# PWM.net
KiCad netlist of a schematic drawn in EAGLE
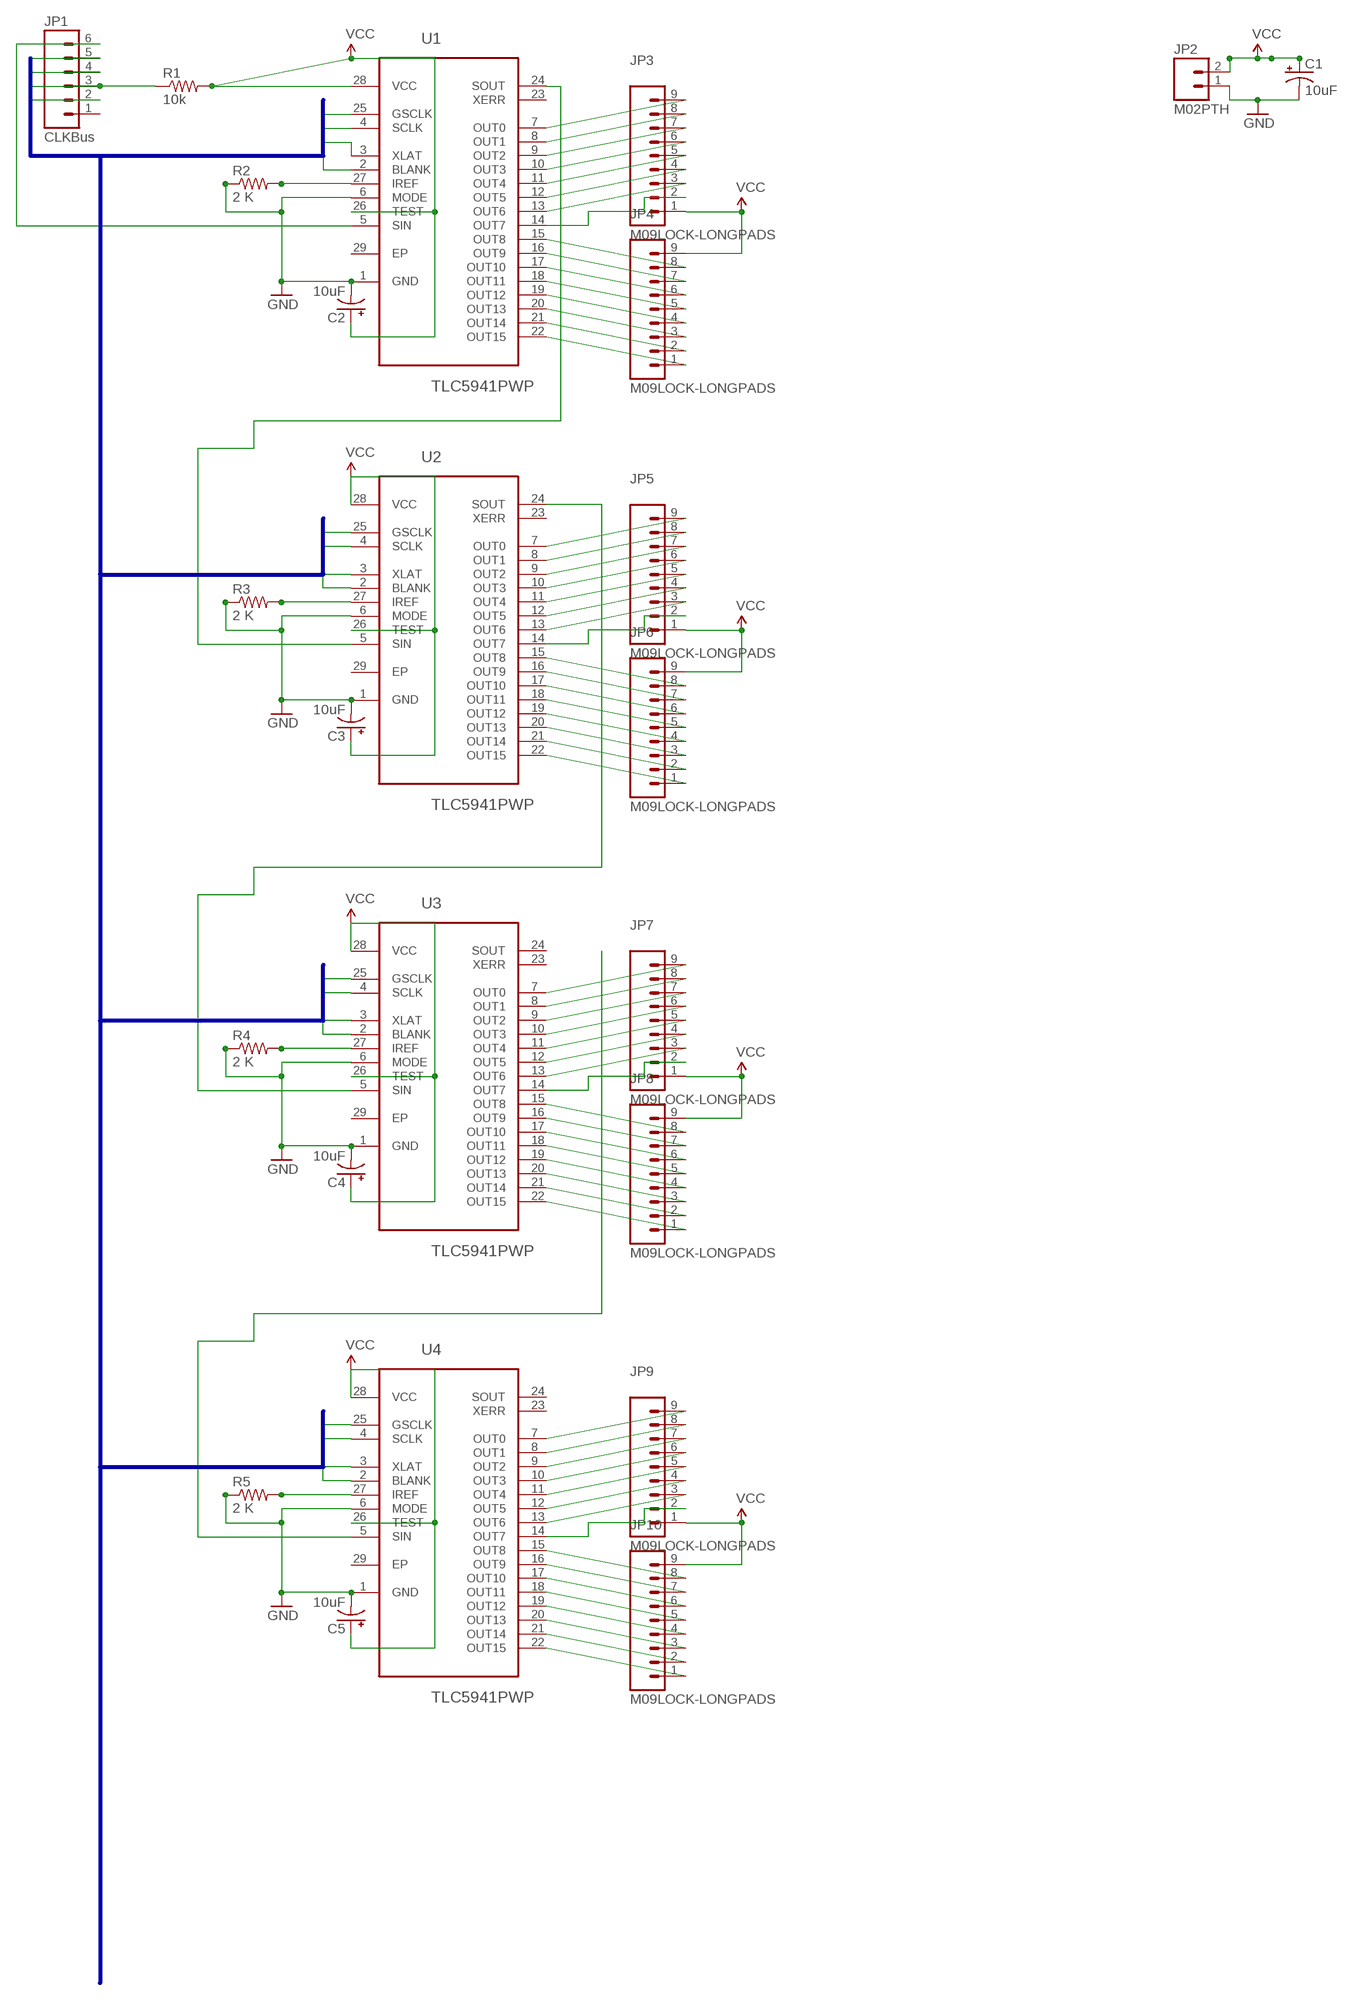
[diagram p0: schematic, sheet 1]

(export (version "E")
  (design (tool "Eeschema 10.0.6"))
  (components
    (comp (ref "C1")
      (value "10uF")
      (footprint "eagle-import:CPOL-RADIAL-10UF-25V")
      (libsource (lib "eagle-import") (part "CAP_POLPTH2"))
    )
    (comp (ref "C2")
      (value "10uF")
      (footprint "eagle-import:CPOL-RADIAL-10UF-25V")
      (libsource (lib "eagle-import") (part "CAP_POLPTH2"))
    )
    (comp (ref "C3")
      (value "10uF")
      (footprint "eagle-import:CPOL-RADIAL-10UF-25V")
      (libsource (lib "eagle-import") (part "CAP_POLPTH2"))
    )
    (comp (ref "C4")
      (value "10uF")
      (footprint "eagle-import:CPOL-RADIAL-10UF-25V")
      (libsource (lib "eagle-import") (part "CAP_POLPTH2"))
    )
    (comp (ref "C5")
      (value "10uF")
      (footprint "eagle-import:CPOL-RADIAL-10UF-25V")
      (libsource (lib "eagle-import") (part "CAP_POLPTH2"))
    )
    (comp (ref "JP1")
      (value "CLKBus")
      (footprint "eagle-import:1X06_LOCK_LONGPADS")
      (libsource (lib "eagle-import") (part "M06LOCK_LONGPADS"))
    )
    (comp (ref "JP2")
      (value "M02PTH")
      (footprint "eagle-import:1X02")
      (libsource (lib "eagle-import") (part "M02PTH"))
    )
    (comp (ref "JP3")
      (value "M09LOCK-LONGPADS")
      (footprint "eagle-import:1X09_LOCK_LONGPADS")
      (libsource (lib "eagle-import") (part "M09LOCK-LONGPADS"))
    )
    (comp (ref "JP4")
      (value "M09LOCK-LONGPADS")
      (footprint "eagle-import:1X09_LOCK_LONGPADS")
      (libsource (lib "eagle-import") (part "M09LOCK-LONGPADS"))
    )
    (comp (ref "JP5")
      (value "M09LOCK-LONGPADS")
      (footprint "eagle-import:1X09_LOCK_LONGPADS")
      (libsource (lib "eagle-import") (part "M09LOCK-LONGPADS"))
    )
    (comp (ref "JP6")
      (value "M09LOCK-LONGPADS")
      (footprint "eagle-import:1X09_LOCK_LONGPADS")
      (libsource (lib "eagle-import") (part "M09LOCK-LONGPADS"))
    )
    (comp (ref "JP7")
      (value "M09LOCK-LONGPADS")
      (footprint "eagle-import:1X09_LOCK_LONGPADS")
      (libsource (lib "eagle-import") (part "M09LOCK-LONGPADS"))
    )
    (comp (ref "JP8")
      (value "M09LOCK-LONGPADS")
      (footprint "eagle-import:1X09_LOCK_LONGPADS")
      (libsource (lib "eagle-import") (part "M09LOCK-LONGPADS"))
    )
    (comp (ref "JP9")
      (value "M09LOCK-LONGPADS")
      (footprint "eagle-import:1X09_LOCK_LONGPADS")
      (libsource (lib "eagle-import") (part "M09LOCK-LONGPADS"))
    )
    (comp (ref "JP10")
      (value "M09LOCK-LONGPADS")
      (footprint "eagle-import:1X09_LOCK_LONGPADS")
      (libsource (lib "eagle-import") (part "M09LOCK-LONGPADS"))
    )
    (comp (ref "R1")
      (value "10k")
      (footprint "eagle-import:AXIAL-0.3")
      (libsource (lib "eagle-import") (part "10KOHM-1/4W-1%(PTH)HORIZ"))
    )
    (comp (ref "R2")
      (value "2 K")
      (footprint "eagle-import:AXIAL-0.3")
      (libsource (lib "eagle-import") (part "1KOHM1/4W5%(PTH)"))
    )
    (comp (ref "R3")
      (value "2 K")
      (footprint "eagle-import:AXIAL-0.3")
      (libsource (lib "eagle-import") (part "1KOHM1/4W5%(PTH)"))
    )
    (comp (ref "R4")
      (value "2 K")
      (footprint "eagle-import:AXIAL-0.3")
      (libsource (lib "eagle-import") (part "1KOHM1/4W5%(PTH)"))
    )
    (comp (ref "R5")
      (value "2 K")
      (footprint "eagle-import:AXIAL-0.3")
      (libsource (lib "eagle-import") (part "1KOHM1/4W5%(PTH)"))
    )
    (comp (ref "U1")
      (value "TLC5941PWP")
      (footprint "eagle-import:SOP65P640X120-29N")
      (libsource (lib "eagle-import") (part "TLC5941PWP"))
    )
    (comp (ref "U2")
      (value "TLC5941PWP")
      (footprint "eagle-import:SOP65P640X120-29N")
      (libsource (lib "eagle-import") (part "TLC5941PWP"))
    )
    (comp (ref "U3")
      (value "TLC5941PWP")
      (footprint "eagle-import:SOP65P640X120-29N")
      (libsource (lib "eagle-import") (part "TLC5941PWP"))
    )
    (comp (ref "U4")
      (value "TLC5941PWP")
      (footprint "eagle-import:SOP65P640X120-29N")
      (libsource (lib "eagle-import") (part "TLC5941PWP"))
    )
  )
  (nets
    (net (code "2") (name "/BLANK") (class "Default")
      (node (ref "JP1") (pin "3") (pinfunction "3_3") (pintype "passive"))
      (node (ref "R1") (pin "P$1") (pinfunction "1_P$1") (pintype "passive"))
      (node (ref "U1") (pin "2") (pinfunction "BLANK_2") (pintype "input"))
      (node (ref "U2") (pin "2") (pinfunction "BLANK_2") (pintype "input"))
      (node (ref "U3") (pin "2") (pinfunction "BLANK_2") (pintype "input"))
      (node (ref "U4") (pin "2") (pinfunction "BLANK_2") (pintype "input"))
    )
    (net (code "3") (name "/CLKBUS:GSCLK") (class "Default")
      (node (ref "JP1") (pin "5") (pinfunction "5_5") (pintype "passive"))
      (node (ref "U1") (pin "4") (pinfunction "SCLK_4") (pintype "input"))
      (node (ref "U2") (pin "4") (pinfunction "SCLK_4") (pintype "input"))
      (node (ref "U3") (pin "4") (pinfunction "SCLK_4") (pintype "input"))
      (node (ref "U4") (pin "4") (pinfunction "SCLK_4") (pintype "input"))
    )
    (net (code "4") (name "/GSCLK") (class "Default")
      (node (ref "JP1") (pin "2") (pinfunction "2_2") (pintype "passive"))
      (node (ref "U1") (pin "25") (pinfunction "GSCLK_25") (pintype "output"))
      (node (ref "U2") (pin "25") (pinfunction "GSCLK_25") (pintype "output"))
      (node (ref "U3") (pin "25") (pinfunction "GSCLK_25") (pintype "output"))
      (node (ref "U4") (pin "25") (pinfunction "GSCLK_25") (pintype "output"))
    )
    (net (code "5") (name "/XLAT") (class "Default")
      (node (ref "JP1") (pin "4") (pinfunction "4_4") (pintype "passive"))
      (node (ref "U1") (pin "3") (pinfunction "XLAT_3") (pintype "input"))
      (node (ref "U2") (pin "3") (pinfunction "XLAT_3") (pintype "input"))
      (node (ref "U3") (pin "3") (pinfunction "XLAT_3") (pintype "input"))
      (node (ref "U4") (pin "3") (pinfunction "XLAT_3") (pintype "input"))
    )
    (net (code "7") (name "GND") (class "Default")
      (node (ref "C1") (pin "2") (pinfunction "-_2") (pintype "passive"))
      (node (ref "C2") (pin "2") (pinfunction "-_2") (pintype "passive"))
      (node (ref "C3") (pin "2") (pinfunction "-_2") (pintype "passive"))
      (node (ref "C4") (pin "2") (pinfunction "-_2") (pintype "passive"))
      (node (ref "C5") (pin "2") (pinfunction "-_2") (pintype "passive"))
      (node (ref "JP2") (pin "1") (pinfunction "1_1") (pintype "passive"))
      (node (ref "R2") (pin "P$1") (pinfunction "1_P$1") (pintype "passive"))
      (node (ref "R3") (pin "P$1") (pinfunction "1_P$1") (pintype "passive"))
      (node (ref "R4") (pin "P$1") (pinfunction "1_P$1") (pintype "passive"))
      (node (ref "R5") (pin "P$1") (pinfunction "1_P$1") (pintype "passive"))
      (node (ref "U1") (pin "1") (pinfunction "GND_1") (pintype "passive"))
      (node (ref "U1") (pin "6") (pinfunction "MODE_6") (pintype "input"))
      (node (ref "U2") (pin "1") (pinfunction "GND_1") (pintype "passive"))
      (node (ref "U2") (pin "6") (pinfunction "MODE_6") (pintype "input"))
      (node (ref "U3") (pin "1") (pinfunction "GND_1") (pintype "passive"))
      (node (ref "U3") (pin "6") (pinfunction "MODE_6") (pintype "input"))
      (node (ref "U4") (pin "1") (pinfunction "GND_1") (pintype "passive"))
      (node (ref "U4") (pin "6") (pinfunction "MODE_6") (pintype "input"))
    )
    (net (code "8") (name "Net-(R2-2)") (class "Default")
      (node (ref "R2") (pin "P$2") (pinfunction "2_P$2") (pintype "passive"))
      (node (ref "U1") (pin "27") (pinfunction "IREF_27") (pintype "input"))
    )
    (net (code "9") (name "Net-(R3-2)") (class "Default")
      (node (ref "R3") (pin "P$2") (pinfunction "2_P$2") (pintype "passive"))
      (node (ref "U2") (pin "27") (pinfunction "IREF_27") (pintype "input"))
    )
    (net (code "10") (name "Net-(R4-2)") (class "Default")
      (node (ref "R4") (pin "P$2") (pinfunction "2_P$2") (pintype "passive"))
      (node (ref "U3") (pin "27") (pinfunction "IREF_27") (pintype "input"))
    )
    (net (code "11") (name "Net-(R5-2)") (class "Default")
      (node (ref "R5") (pin "P$2") (pinfunction "2_P$2") (pintype "passive"))
      (node (ref "U4") (pin "27") (pinfunction "IREF_27") (pintype "input"))
    )
    (net (code "12") (name "Net-(U1-OUT0)") (class "Default")
      (node (ref "JP3") (pin "9") (pinfunction "9_9") (pintype "passive"))
      (node (ref "U1") (pin "7") (pinfunction "OUT0_7") (pintype "output"))
    )
    (net (code "13") (name "Net-(U1-OUT1)") (class "Default")
      (node (ref "JP3") (pin "8") (pinfunction "8_8") (pintype "passive"))
      (node (ref "U1") (pin "8") (pinfunction "OUT1_8") (pintype "output"))
    )
    (net (code "14") (name "Net-(U1-OUT2)") (class "Default")
      (node (ref "JP3") (pin "7") (pinfunction "7_7") (pintype "passive"))
      (node (ref "U1") (pin "9") (pinfunction "OUT2_9") (pintype "output"))
    )
    (net (code "15") (name "Net-(U1-OUT3)") (class "Default")
      (node (ref "JP3") (pin "6") (pinfunction "6_6") (pintype "passive"))
      (node (ref "U1") (pin "10") (pinfunction "OUT3_10") (pintype "output"))
    )
    (net (code "16") (name "Net-(U1-OUT4)") (class "Default")
      (node (ref "JP3") (pin "5") (pinfunction "5_5") (pintype "passive"))
      (node (ref "U1") (pin "11") (pinfunction "OUT4_11") (pintype "output"))
    )
    (net (code "17") (name "Net-(U1-OUT5)") (class "Default")
      (node (ref "JP3") (pin "4") (pinfunction "4_4") (pintype "passive"))
      (node (ref "U1") (pin "12") (pinfunction "OUT5_12") (pintype "output"))
    )
    (net (code "18") (name "Net-(U1-OUT6)") (class "Default")
      (node (ref "JP3") (pin "3") (pinfunction "3_3") (pintype "passive"))
      (node (ref "U1") (pin "13") (pinfunction "OUT6_13") (pintype "output"))
    )
    (net (code "19") (name "Net-(U1-OUT7)") (class "Default")
      (node (ref "JP3") (pin "2") (pinfunction "2_2") (pintype "passive"))
      (node (ref "U1") (pin "14") (pinfunction "OUT7_14") (pintype "output"))
    )
    (net (code "20") (name "Net-(U1-OUT8)") (class "Default")
      (node (ref "JP4") (pin "8") (pinfunction "8_8") (pintype "passive"))
      (node (ref "U1") (pin "15") (pinfunction "OUT8_15") (pintype "output"))
    )
    (net (code "21") (name "Net-(U1-OUT9)") (class "Default")
      (node (ref "JP4") (pin "7") (pinfunction "7_7") (pintype "passive"))
      (node (ref "U1") (pin "16") (pinfunction "OUT9_16") (pintype "output"))
    )
    (net (code "22") (name "Net-(U1-OUT10)") (class "Default")
      (node (ref "JP4") (pin "6") (pinfunction "6_6") (pintype "passive"))
      (node (ref "U1") (pin "17") (pinfunction "OUT10_17") (pintype "output"))
    )
    (net (code "23") (name "Net-(U1-OUT11)") (class "Default")
      (node (ref "JP4") (pin "5") (pinfunction "5_5") (pintype "passive"))
      (node (ref "U1") (pin "18") (pinfunction "OUT11_18") (pintype "output"))
    )
    (net (code "24") (name "Net-(U1-OUT12)") (class "Default")
      (node (ref "JP4") (pin "4") (pinfunction "4_4") (pintype "passive"))
      (node (ref "U1") (pin "19") (pinfunction "OUT12_19") (pintype "output"))
    )
    (net (code "25") (name "Net-(U1-OUT13)") (class "Default")
      (node (ref "JP4") (pin "3") (pinfunction "3_3") (pintype "passive"))
      (node (ref "U1") (pin "20") (pinfunction "OUT13_20") (pintype "output"))
    )
    (net (code "26") (name "Net-(U1-OUT14)") (class "Default")
      (node (ref "JP4") (pin "2") (pinfunction "2_2") (pintype "passive"))
      (node (ref "U1") (pin "21") (pinfunction "OUT14_21") (pintype "output"))
    )
    (net (code "27") (name "Net-(U1-OUT15)") (class "Default")
      (node (ref "JP4") (pin "1") (pinfunction "1_1") (pintype "passive"))
      (node (ref "U1") (pin "22") (pinfunction "OUT15_22") (pintype "output"))
    )
    (net (code "28") (name "Net-(U1-SIN)") (class "Default")
      (node (ref "JP1") (pin "6") (pinfunction "6_6") (pintype "passive"))
      (node (ref "U1") (pin "5") (pinfunction "SIN_5") (pintype "input"))
    )
    (net (code "29") (name "Net-(U1-SOUT)") (class "Default")
      (node (ref "U1") (pin "24") (pinfunction "SOUT_24") (pintype "output"))
      (node (ref "U2") (pin "5") (pinfunction "SIN_5") (pintype "input"))
    )
    (net (code "30") (name "Net-(U2-OUT0)") (class "Default")
      (node (ref "JP5") (pin "9") (pinfunction "9_9") (pintype "passive"))
      (node (ref "U2") (pin "7") (pinfunction "OUT0_7") (pintype "output"))
    )
    (net (code "31") (name "Net-(U2-OUT1)") (class "Default")
      (node (ref "JP5") (pin "8") (pinfunction "8_8") (pintype "passive"))
      (node (ref "U2") (pin "8") (pinfunction "OUT1_8") (pintype "output"))
    )
    (net (code "32") (name "Net-(U2-OUT2)") (class "Default")
      (node (ref "JP5") (pin "7") (pinfunction "7_7") (pintype "passive"))
      (node (ref "U2") (pin "9") (pinfunction "OUT2_9") (pintype "output"))
    )
    (net (code "33") (name "Net-(U2-OUT3)") (class "Default")
      (node (ref "JP5") (pin "6") (pinfunction "6_6") (pintype "passive"))
      (node (ref "U2") (pin "10") (pinfunction "OUT3_10") (pintype "output"))
    )
    (net (code "34") (name "Net-(U2-OUT4)") (class "Default")
      (node (ref "JP5") (pin "5") (pinfunction "5_5") (pintype "passive"))
      (node (ref "U2") (pin "11") (pinfunction "OUT4_11") (pintype "output"))
    )
    (net (code "35") (name "Net-(U2-OUT5)") (class "Default")
      (node (ref "JP5") (pin "4") (pinfunction "4_4") (pintype "passive"))
      (node (ref "U2") (pin "12") (pinfunction "OUT5_12") (pintype "output"))
    )
    (net (code "36") (name "Net-(U2-OUT6)") (class "Default")
      (node (ref "JP5") (pin "3") (pinfunction "3_3") (pintype "passive"))
      (node (ref "U2") (pin "13") (pinfunction "OUT6_13") (pintype "output"))
    )
    (net (code "37") (name "Net-(U2-OUT7)") (class "Default")
      (node (ref "JP5") (pin "2") (pinfunction "2_2") (pintype "passive"))
      (node (ref "U2") (pin "14") (pinfunction "OUT7_14") (pintype "output"))
    )
    (net (code "38") (name "Net-(U2-OUT8)") (class "Default")
      (node (ref "JP6") (pin "8") (pinfunction "8_8") (pintype "passive"))
      (node (ref "U2") (pin "15") (pinfunction "OUT8_15") (pintype "output"))
    )
    (net (code "39") (name "Net-(U2-OUT9)") (class "Default")
      (node (ref "JP6") (pin "7") (pinfunction "7_7") (pintype "passive"))
      (node (ref "U2") (pin "16") (pinfunction "OUT9_16") (pintype "output"))
    )
    (net (code "40") (name "Net-(U2-OUT10)") (class "Default")
      (node (ref "JP6") (pin "6") (pinfunction "6_6") (pintype "passive"))
      (node (ref "U2") (pin "17") (pinfunction "OUT10_17") (pintype "output"))
    )
    (net (code "41") (name "Net-(U2-OUT11)") (class "Default")
      (node (ref "JP6") (pin "5") (pinfunction "5_5") (pintype "passive"))
      (node (ref "U2") (pin "18") (pinfunction "OUT11_18") (pintype "output"))
    )
    (net (code "42") (name "Net-(U2-OUT12)") (class "Default")
      (node (ref "JP6") (pin "4") (pinfunction "4_4") (pintype "passive"))
      (node (ref "U2") (pin "19") (pinfunction "OUT12_19") (pintype "output"))
    )
    (net (code "43") (name "Net-(U2-OUT13)") (class "Default")
      (node (ref "JP6") (pin "3") (pinfunction "3_3") (pintype "passive"))
      (node (ref "U2") (pin "20") (pinfunction "OUT13_20") (pintype "output"))
    )
    (net (code "44") (name "Net-(U2-OUT14)") (class "Default")
      (node (ref "JP6") (pin "2") (pinfunction "2_2") (pintype "passive"))
      (node (ref "U2") (pin "21") (pinfunction "OUT14_21") (pintype "output"))
    )
    (net (code "45") (name "Net-(U2-OUT15)") (class "Default")
      (node (ref "JP6") (pin "1") (pinfunction "1_1") (pintype "passive"))
      (node (ref "U2") (pin "22") (pinfunction "OUT15_22") (pintype "output"))
    )
    (net (code "46") (name "Net-(U2-SOUT)") (class "Default")
      (node (ref "U2") (pin "24") (pinfunction "SOUT_24") (pintype "output"))
      (node (ref "U3") (pin "5") (pinfunction "SIN_5") (pintype "input"))
    )
    (net (code "47") (name "Net-(U3-OUT0)") (class "Default")
      (node (ref "JP7") (pin "9") (pinfunction "9_9") (pintype "passive"))
      (node (ref "U3") (pin "7") (pinfunction "OUT0_7") (pintype "output"))
    )
    (net (code "48") (name "Net-(U3-OUT1)") (class "Default")
      (node (ref "JP7") (pin "8") (pinfunction "8_8") (pintype "passive"))
      (node (ref "U3") (pin "8") (pinfunction "OUT1_8") (pintype "output"))
    )
    (net (code "49") (name "Net-(U3-OUT2)") (class "Default")
      (node (ref "JP7") (pin "7") (pinfunction "7_7") (pintype "passive"))
      (node (ref "U3") (pin "9") (pinfunction "OUT2_9") (pintype "output"))
    )
    (net (code "50") (name "Net-(U3-OUT3)") (class "Default")
      (node (ref "JP7") (pin "6") (pinfunction "6_6") (pintype "passive"))
      (node (ref "U3") (pin "10") (pinfunction "OUT3_10") (pintype "output"))
    )
    (net (code "51") (name "Net-(U3-OUT4)") (class "Default")
      (node (ref "JP7") (pin "5") (pinfunction "5_5") (pintype "passive"))
      (node (ref "U3") (pin "11") (pinfunction "OUT4_11") (pintype "output"))
    )
    (net (code "52") (name "Net-(U3-OUT5)") (class "Default")
      (node (ref "JP7") (pin "4") (pinfunction "4_4") (pintype "passive"))
      (node (ref "U3") (pin "12") (pinfunction "OUT5_12") (pintype "output"))
    )
    (net (code "53") (name "Net-(U3-OUT6)") (class "Default")
      (node (ref "JP7") (pin "3") (pinfunction "3_3") (pintype "passive"))
      (node (ref "U3") (pin "13") (pinfunction "OUT6_13") (pintype "output"))
    )
    (net (code "54") (name "Net-(U3-OUT7)") (class "Default")
      (node (ref "JP7") (pin "2") (pinfunction "2_2") (pintype "passive"))
      (node (ref "U3") (pin "14") (pinfunction "OUT7_14") (pintype "output"))
    )
    (net (code "55") (name "Net-(U3-OUT8)") (class "Default")
      (node (ref "JP8") (pin "8") (pinfunction "8_8") (pintype "passive"))
      (node (ref "U3") (pin "15") (pinfunction "OUT8_15") (pintype "output"))
    )
    (net (code "56") (name "Net-(U3-OUT9)") (class "Default")
      (node (ref "JP8") (pin "7") (pinfunction "7_7") (pintype "passive"))
      (node (ref "U3") (pin "16") (pinfunction "OUT9_16") (pintype "output"))
    )
    (net (code "57") (name "Net-(U3-OUT10)") (class "Default")
      (node (ref "JP8") (pin "6") (pinfunction "6_6") (pintype "passive"))
      (node (ref "U3") (pin "17") (pinfunction "OUT10_17") (pintype "output"))
    )
    (net (code "58") (name "Net-(U3-OUT11)") (class "Default")
      (node (ref "JP8") (pin "5") (pinfunction "5_5") (pintype "passive"))
      (node (ref "U3") (pin "18") (pinfunction "OUT11_18") (pintype "output"))
    )
    (net (code "59") (name "Net-(U3-OUT12)") (class "Default")
      (node (ref "JP8") (pin "4") (pinfunction "4_4") (pintype "passive"))
      (node (ref "U3") (pin "19") (pinfunction "OUT12_19") (pintype "output"))
    )
    (net (code "60") (name "Net-(U3-OUT13)") (class "Default")
      (node (ref "JP8") (pin "3") (pinfunction "3_3") (pintype "passive"))
      (node (ref "U3") (pin "20") (pinfunction "OUT13_20") (pintype "output"))
    )
    (net (code "61") (name "Net-(U3-OUT14)") (class "Default")
      (node (ref "JP8") (pin "2") (pinfunction "2_2") (pintype "passive"))
      (node (ref "U3") (pin "21") (pinfunction "OUT14_21") (pintype "output"))
    )
    (net (code "62") (name "Net-(U3-OUT15)") (class "Default")
      (node (ref "JP8") (pin "1") (pinfunction "1_1") (pintype "passive"))
      (node (ref "U3") (pin "22") (pinfunction "OUT15_22") (pintype "output"))
    )
    (net (code "63") (name "Net-(U4-OUT0)") (class "Default")
      (node (ref "JP9") (pin "9") (pinfunction "9_9") (pintype "passive"))
      (node (ref "U4") (pin "7") (pinfunction "OUT0_7") (pintype "output"))
    )
    (net (code "64") (name "Net-(U4-OUT1)") (class "Default")
      (node (ref "JP9") (pin "8") (pinfunction "8_8") (pintype "passive"))
      (node (ref "U4") (pin "8") (pinfunction "OUT1_8") (pintype "output"))
    )
    (net (code "65") (name "Net-(U4-OUT2)") (class "Default")
      (node (ref "JP9") (pin "7") (pinfunction "7_7") (pintype "passive"))
      (node (ref "U4") (pin "9") (pinfunction "OUT2_9") (pintype "output"))
    )
    (net (code "66") (name "Net-(U4-OUT3)") (class "Default")
      (node (ref "JP9") (pin "6") (pinfunction "6_6") (pintype "passive"))
      (node (ref "U4") (pin "10") (pinfunction "OUT3_10") (pintype "output"))
    )
    (net (code "67") (name "Net-(U4-OUT4)") (class "Default")
      (node (ref "JP9") (pin "5") (pinfunction "5_5") (pintype "passive"))
      (node (ref "U4") (pin "11") (pinfunction "OUT4_11") (pintype "output"))
    )
    (net (code "68") (name "Net-(U4-OUT5)") (class "Default")
      (node (ref "JP9") (pin "4") (pinfunction "4_4") (pintype "passive"))
      (node (ref "U4") (pin "12") (pinfunction "OUT5_12") (pintype "output"))
    )
    (net (code "69") (name "Net-(U4-OUT6)") (class "Default")
      (node (ref "JP9") (pin "3") (pinfunction "3_3") (pintype "passive"))
      (node (ref "U4") (pin "13") (pinfunction "OUT6_13") (pintype "output"))
    )
    (net (code "70") (name "Net-(U4-OUT7)") (class "Default")
      (node (ref "JP9") (pin "2") (pinfunction "2_2") (pintype "passive"))
      (node (ref "U4") (pin "14") (pinfunction "OUT7_14") (pintype "output"))
    )
    (net (code "71") (name "Net-(U4-OUT8)") (class "Default")
      (node (ref "JP10") (pin "8") (pinfunction "8_8") (pintype "passive"))
      (node (ref "U4") (pin "15") (pinfunction "OUT8_15") (pintype "output"))
    )
    (net (code "72") (name "Net-(U4-OUT9)") (class "Default")
      (node (ref "JP10") (pin "7") (pinfunction "7_7") (pintype "passive"))
      (node (ref "U4") (pin "16") (pinfunction "OUT9_16") (pintype "output"))
    )
    (net (code "73") (name "Net-(U4-OUT10)") (class "Default")
      (node (ref "JP10") (pin "6") (pinfunction "6_6") (pintype "passive"))
      (node (ref "U4") (pin "17") (pinfunction "OUT10_17") (pintype "output"))
    )
    (net (code "74") (name "Net-(U4-OUT11)") (class "Default")
      (node (ref "JP10") (pin "5") (pinfunction "5_5") (pintype "passive"))
      (node (ref "U4") (pin "18") (pinfunction "OUT11_18") (pintype "output"))
    )
    (net (code "75") (name "Net-(U4-OUT12)") (class "Default")
      (node (ref "JP10") (pin "4") (pinfunction "4_4") (pintype "passive"))
      (node (ref "U4") (pin "19") (pinfunction "OUT12_19") (pintype "output"))
    )
    (net (code "76") (name "Net-(U4-OUT13)") (class "Default")
      (node (ref "JP10") (pin "3") (pinfunction "3_3") (pintype "passive"))
      (node (ref "U4") (pin "20") (pinfunction "OUT13_20") (pintype "output"))
    )
    (net (code "77") (name "Net-(U4-OUT14)") (class "Default")
      (node (ref "JP10") (pin "2") (pinfunction "2_2") (pintype "passive"))
      (node (ref "U4") (pin "21") (pinfunction "OUT14_21") (pintype "output"))
    )
    (net (code "78") (name "Net-(U4-OUT15)") (class "Default")
      (node (ref "JP10") (pin "1") (pinfunction "1_1") (pintype "passive"))
      (node (ref "U4") (pin "22") (pinfunction "OUT15_22") (pintype "output"))
    )
    (net (code "79") (name "VCC") (class "Default")
      (node (ref "C1") (pin "1") (pinfunction "+_1") (pintype "passive"))
      (node (ref "C2") (pin "1") (pinfunction "+_1") (pintype "passive"))
      (node (ref "C3") (pin "1") (pinfunction "+_1") (pintype "passive"))
      (node (ref "C4") (pin "1") (pinfunction "+_1") (pintype "passive"))
      (node (ref "C5") (pin "1") (pinfunction "+_1") (pintype "passive"))
      (node (ref "JP10") (pin "9") (pinfunction "9_9") (pintype "passive"))
      (node (ref "JP2") (pin "2") (pinfunction "2_2") (pintype "passive"))
      (node (ref "JP3") (pin "1") (pinfunction "1_1") (pintype "passive"))
      (node (ref "JP4") (pin "9") (pinfunction "9_9") (pintype "passive"))
      (node (ref "JP5") (pin "1") (pinfunction "1_1") (pintype "passive"))
      (node (ref "JP6") (pin "9") (pinfunction "9_9") (pintype "passive"))
      (node (ref "JP7") (pin "1") (pinfunction "1_1") (pintype "passive"))
      (node (ref "JP8") (pin "9") (pinfunction "9_9") (pintype "passive"))
      (node (ref "JP9") (pin "1") (pinfunction "1_1") (pintype "passive"))
      (node (ref "R1") (pin "P$2") (pinfunction "2_P$2") (pintype "passive"))
      (node (ref "U1") (pin "26") (pinfunction "TEST_26") (pintype "input"))
      (node (ref "U1") (pin "28") (pinfunction "VCC_28") (pintype "power_in"))
      (node (ref "U2") (pin "26") (pinfunction "TEST_26") (pintype "input"))
      (node (ref "U2") (pin "28") (pinfunction "VCC_28") (pintype "power_in"))
      (node (ref "U3") (pin "26") (pinfunction "TEST_26") (pintype "input"))
      (node (ref "U3") (pin "28") (pinfunction "VCC_28") (pintype "power_in"))
      (node (ref "U4") (pin "26") (pinfunction "TEST_26") (pintype "input"))
      (node (ref "U4") (pin "28") (pinfunction "VCC_28") (pintype "power_in"))
    )
    (net (code "80") (name "unconnected-(JP1-Pad1)") (class "Default")
      (node (ref "JP1") (pin "1") (pinfunction "1_1") (pintype "passive"))
    )
    (net (code "81") (name "unconnected-(U1-EP-Pad29)") (class "Default")
      (node (ref "U1") (pin "29") (pinfunction "EP_29") (pintype "passive"))
    )
    (net (code "82") (name "unconnected-(U1-XERR-Pad23)") (class "Default")
      (node (ref "U1") (pin "23") (pinfunction "XERR_23") (pintype "output"))
    )
    (net (code "83") (name "unconnected-(U2-EP-Pad29)") (class "Default")
      (node (ref "U2") (pin "29") (pinfunction "EP_29") (pintype "passive"))
    )
    (net (code "84") (name "unconnected-(U2-XERR-Pad23)") (class "Default")
      (node (ref "U2") (pin "23") (pinfunction "XERR_23") (pintype "output"))
    )
    (net (code "85") (name "unconnected-(U3-EP-Pad29)") (class "Default")
      (node (ref "U3") (pin "29") (pinfunction "EP_29") (pintype "passive"))
    )
    (net (code "86") (name "unconnected-(U3-SOUT-Pad24)") (class "Default")
      (node (ref "U3") (pin "24") (pinfunction "SOUT_24") (pintype "output"))
    )
    (net (code "87") (name "unconnected-(U3-XERR-Pad23)") (class "Default")
      (node (ref "U3") (pin "23") (pinfunction "XERR_23") (pintype "output"))
    )
    (net (code "88") (name "unconnected-(U4-EP-Pad29)") (class "Default")
      (node (ref "U4") (pin "29") (pinfunction "EP_29") (pintype "passive"))
    )
    (net (code "89") (name "unconnected-(U4-SIN-Pad5)") (class "Default")
      (node (ref "U4") (pin "5") (pinfunction "SIN_5") (pintype "input"))
    )
    (net (code "90") (name "unconnected-(U4-SOUT-Pad24)") (class "Default")
      (node (ref "U4") (pin "24") (pinfunction "SOUT_24") (pintype "output"))
    )
    (net (code "91") (name "unconnected-(U4-XERR-Pad23)") (class "Default")
      (node (ref "U4") (pin "23") (pinfunction "XERR_23") (pintype "output"))
    )
  )
)
